# CH32V407WEU-R0.net
KiCad netlist of a schematic drawn in Altium Designer
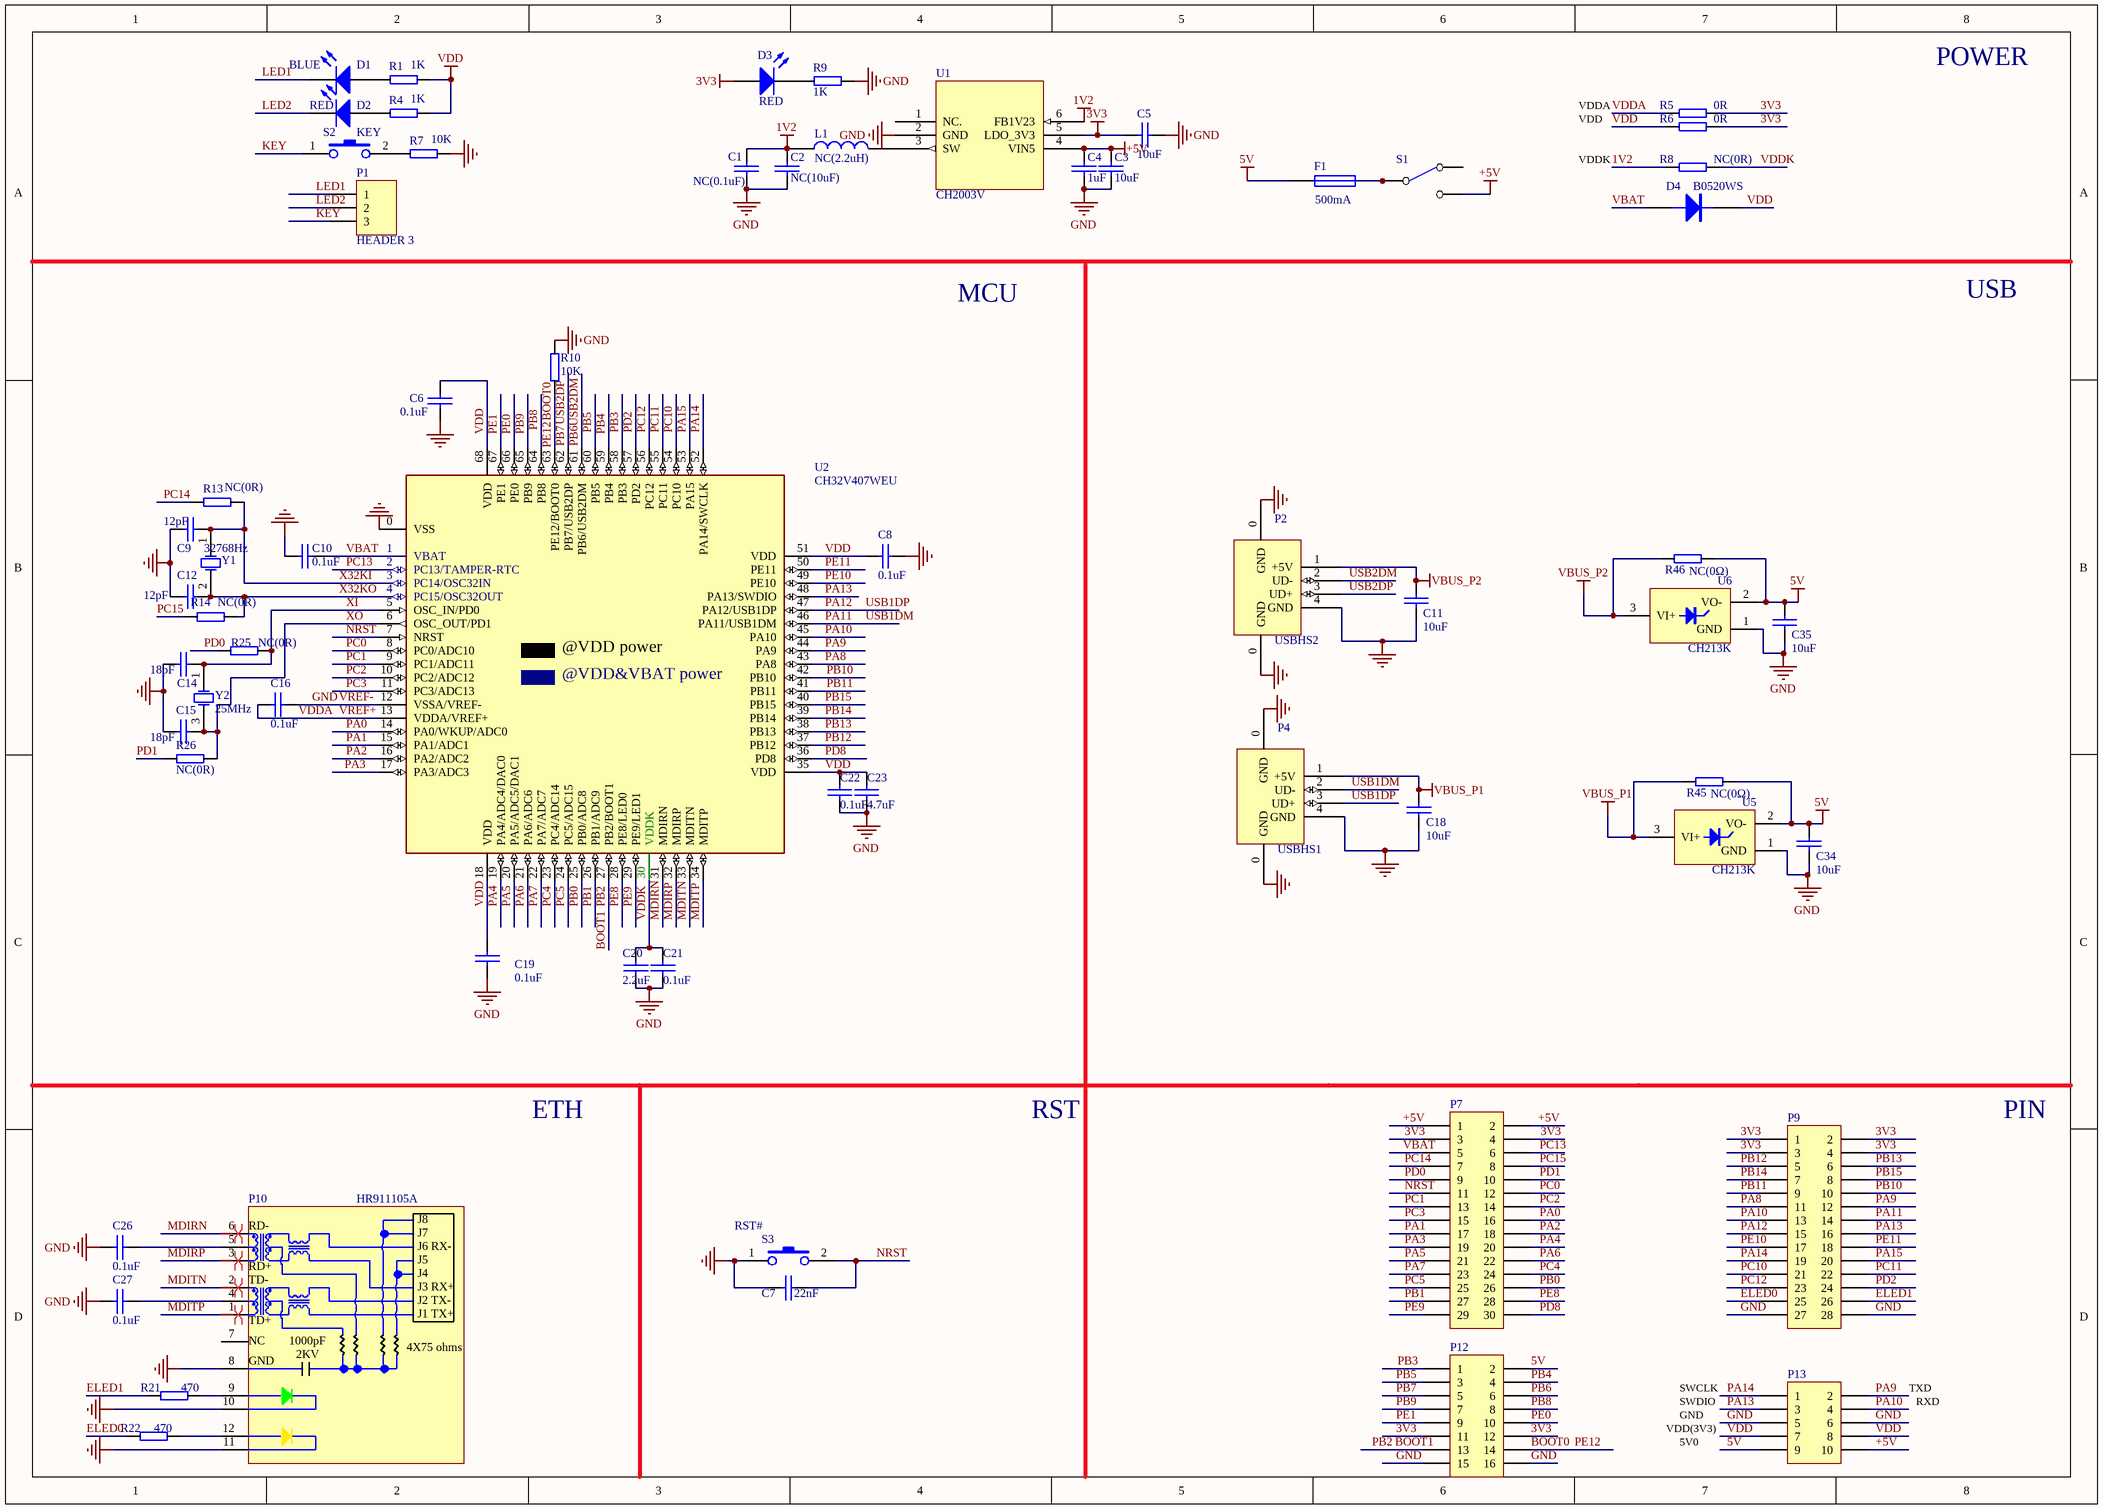
[diagram p0: CH32V407WEU-R0.SchDoc]

(export (version "E")
  (design (tool "Eeschema 10.0.6"))
  (components
    (comp (ref "C1")
      (value "NC(0.1uF)")
      (footprint "0402_C")
      (description "Capacitor")
      (libsource (lib "") (part "CAP_2"))
    )
    (comp (ref "C2")
      (value "NC(10uF)")
      (footprint "0603_C")
      (description "Capacitor")
      (libsource (lib "") (part "CAP_1"))
    )
    (comp (ref "C3")
      (value "10uF")
      (footprint "0603_C")
      (description "Capacitor")
      (libsource (lib "") (part "CAP_1"))
    )
    (comp (ref "C4")
      (value "1uF")
      (footprint "0402_C")
      (description "Capacitor")
      (libsource (lib "") (part "CAP_2"))
    )
    (comp (ref "C5")
      (value "10uF")
      (footprint "0603_C")
      (description "Capacitor")
      (libsource (lib "") (part "CAP_1"))
    )
    (comp (ref "C6")
      (value "0.1uF")
      (footprint "0402_C")
      (description "Capacitor")
      (libsource (lib "") (part "CAP_1"))
    )
    (comp (ref "C7")
      (value "22nF")
      (footprint "0402_C")
      (description "Capacitor")
      (libsource (lib "*") (part "CAP"))
    )
    (comp (ref "C8")
      (value "0.1uF")
      (footprint "0402_C")
      (description "Capacitor")
      (libsource (lib "") (part "CAP_1"))
    )
    (comp (ref "C9")
      (value "12pF")
      (footprint "0402_C")
      (description "Capacitor")
      (libsource (lib "") (part "CAP_1"))
    )
    (comp (ref "C10")
      (value "0.1uF")
      (footprint "0402_C")
      (description "Capacitor")
      (libsource (lib "") (part "CAP_1"))
    )
    (comp (ref "C11")
      (value "10uF")
      (footprint "0603_C")
      (description "Capacitor")
      (libsource (lib "*") (part "CAP"))
    )
    (comp (ref "C12")
      (value "12pF")
      (footprint "0402_C")
      (description "Capacitor")
      (libsource (lib "") (part "CAP_1"))
    )
    (comp (ref "C14")
      (value "18pF")
      (footprint "0402_C")
      (description "Capacitor")
      (libsource (lib "") (part "CAP_1"))
    )
    (comp (ref "C15")
      (value "18pF")
      (footprint "0402_C")
      (description "Capacitor")
      (libsource (lib "") (part "CAP_1"))
    )
    (comp (ref "C16")
      (value "0.1uF")
      (footprint "0402_C")
      (description "Capacitor")
      (libsource (lib "") (part "CAP_1"))
    )
    (comp (ref "C18")
      (value "10uF")
      (footprint "0603_C")
      (description "Capacitor")
      (libsource (lib "*") (part "CAP"))
    )
    (comp (ref "C19")
      (value "0.1uF")
      (footprint "0402_C")
      (description "Capacitor")
      (libsource (lib "") (part "CAP_1"))
    )
    (comp (ref "C20")
      (value "2.2uF")
      (footprint "0402_C")
      (description "Capacitor")
      (libsource (lib "") (part "CAP_1"))
    )
    (comp (ref "C21")
      (value "0.1uF")
      (footprint "0402_C")
      (description "Capacitor")
      (libsource (lib "") (part "CAP_1"))
    )
    (comp (ref "C22")
      (value "0.1uF")
      (footprint "0402_C")
      (description "Capacitor")
      (libsource (lib "") (part "CAP_1"))
    )
    (comp (ref "C23")
      (value "4.7uF")
      (footprint "0402_C")
      (description "Capacitor")
      (libsource (lib "") (part "CAP_1"))
    )
    (comp (ref "C26")
      (value "0.1uF")
      (footprint "0402_C")
      (description "Capacitor")
      (libsource (lib "wch_sch_others") (part "CAP"))
    )
    (comp (ref "C27")
      (value "0.1uF")
      (footprint "0402_C")
      (description "Capacitor")
      (libsource (lib "wch_sch_others") (part "CAP"))
    )
    (comp (ref "C34")
      (value "10uF")
      (footprint "0603_C")
      (description "Capacitor")
      (libsource (lib "*") (part "CAP"))
    )
    (comp (ref "C35")
      (value "10uF")
      (footprint "0603_C")
      (description "Capacitor")
      (libsource (lib "*") (part "CAP"))
    )
    (comp (ref "D1")
      (value "BLUE")
      (footprint "0603+")
      (description "Typical INFRARED GaAs LED")
      (fields (field (name "PUBLISHER") "Altium Limited"))
      (libsource (lib "*") (part "LED0"))
    )
    (comp (ref "D2")
      (value "RED")
      (footprint "0603+")
      (description "Typical INFRARED GaAs LED")
      (fields (field (name "PUBLISHER") "Altium Limited"))
      (libsource (lib "*") (part "LED0"))
    )
    (comp (ref "D3")
      (value "RED")
      (footprint "0603+")
      (description "Typical INFRARED GaAs LED")
      (fields (field (name "PUBLISHER") "Altium Limited"))
      (libsource (lib "*") (part "LED0"))
    )
    (comp (ref "D4")
      (value "B0520WS")
      (footprint "SOD-323")
      (description "Diode")
      (libsource (lib "*") (part "DIODE"))
    )
    (comp (ref "F1")
      (value "500mA")
      (footprint "0603")
      (description "Fuse")
      (libsource (lib "wch_sch_others") (part "FUSE1"))
    )
    (comp (ref "L1") (value "NC(2.2uH)") (footprint "CD32") (libsource (lib "*") (part "INDUCTOR")))
    (comp (ref "P1")
      (value "HEADER 3")
      (footprint "SIP3-2.54MM")
      (description "Header, 3-Pin")
      (libsource (lib "wch_sch_others") (part "HEADER 3"))
    )
    (comp (ref "P2")
      (value "USBHS2")
      (footprint "USBAF")
      (description "USB Port")
      (libsource (lib "*") (part "USB"))
    )
    (comp (ref "P4")
      (value "USBHS1")
      (footprint "USBAF")
      (description "USB Port")
      (libsource (lib "*") (part "USB"))
    )
    (comp (ref "P7")
      (value "HEADER 15x2")
      (footprint "MYPCB:IDC30-2.54MM")
      (description "Header, 15-Pin, Dual row")
      (libsource (lib "wch_sch_others") (part "HEADER 15x2"))
    )
    (comp (ref "P9")
      (value "HEADER 14x2")
      (footprint "MYPCB:IDC28-2.54MM")
      (description "Header, 14-Pin, Dual row")
      (libsource (lib "wch_sch_others") (part "HEADER 14x2"))
    )
    (comp (ref "P10") (value "HR911105A") (footprint "HR911105A") (libsource (lib "*") (part "HR911105A")))
    (comp (ref "P12")
      (value "Ppin")
      (footprint "IDC16-2.54mm")
      (description "Header, 8-Pin, Dual row, Right Angle")
      (fields (field (name "PUBLISHER") "Altium Limited"))
      (libsource (lib "Miscellaneous Connectors") (part "Header 8X2H"))
    )
    (comp (ref "P13")
      (value "LINK")
      (footprint "IDC10-2.54mm")
      (description "Header, 5-Pin, Dual row, Right Angle")
      (fields (field (name "PUBLISHER") "Altium Limited"))
      (libsource (lib "Miscellaneous Connectors") (part "Header 5X2H"))
    )
    (comp (ref "R1") (value "1K") (footprint "0402") (libsource (lib "wch_sch_others") (part "RES")))
    (comp (ref "R4") (value "1K") (footprint "0402") (libsource (lib "wch_sch_others") (part "RES")))
    (comp (ref "R5") (value "0R") (footprint "0402") (libsource (lib "*") (part "R")))
    (comp (ref "R6") (value "0R") (footprint "0402") (libsource (lib "*") (part "R")))
    (comp (ref "R7") (value "10K") (footprint "0402") (libsource (lib "wch_sch_others") (part "RES")))
    (comp (ref "R8") (value "NC(0R)") (footprint "0402") (libsource (lib "*") (part "R")))
    (comp (ref "R9") (value "1K") (footprint "0402") (libsource (lib "wch_sch_others") (part "RES")))
    (comp (ref "R10") (value "10K") (footprint "0402") (libsource (lib "wch_sch_others") (part "RES")))
    (comp (ref "R13") (value "NC(0R)") (footprint "0402") (libsource (lib "wch_sch_others") (part "RES")))
    (comp (ref "R14") (value "NC(0R)") (footprint "0402") (libsource (lib "wch_sch_others") (part "RES")))
    (comp (ref "R21") (value "470") (footprint "0402") (libsource (lib "wch_sch_others") (part "RES")))
    (comp (ref "R22") (value "470") (footprint "0402") (libsource (lib "wch_sch_others") (part "RES")))
    (comp (ref "R25") (value "NC(0R)") (footprint "0402") (libsource (lib "wch_sch_others") (part "RES")))
    (comp (ref "R26") (value "NC(0R)") (footprint "0402") (libsource (lib "wch_sch_others") (part "RES")))
    (comp (ref "R45") (value "NC(0Ω)") (footprint "0402") (libsource (lib "wch_sch_others") (part "RES")))
    (comp (ref "R46") (value "NC(0Ω)") (footprint "0402") (libsource (lib "wch_sch_others") (part "RES")))
    (comp (ref "S1") (value "SW SPDT") (footprint "SW1") (libsource (lib "*") (part "SW SPDT")))
    (comp (ref "S2")
      (value "KEY")
      (footprint "SMD_6.1x3.65x2.5mm-KEY")
      (libsource (lib "wch_sch_others") (part "KEY1"))
    )
    (comp (ref "S3")
      (value "RST#")
      (footprint "SMD_6.1x3.65x2.5mm-KEY")
      (libsource (lib "wch_sch_others") (part "KEY1"))
    )
    (comp (ref "U1")
      (value "CH2003V")
      (footprint "SOT-23-6")
      (description "Step-Down DC-DC Converter, 5V input, 1.23V * 800mA output, with LDO 3.3V * 200mA")
      (libsource (lib "CHXXX") (part "CH2003V"))
    )
    (comp (ref "U2")
      (value "CH32V407WEU")
      (footprint "QFN68_8X8")
      (description "RISC-V FPU HD-MCU, 175MHz, USB_480M, 100M Ethernet & Phy, CAN, ADC, DAC")
      (libsource (lib "CHXXX") (part "CH32V407WEU"))
    )
    (comp (ref "U5")
      (value "CH213K")
      (footprint "SOT-23-3")
      (description "Ideal Diode 5V*1A")
      (libsource (lib "*") (part "CH213K"))
    )
    (comp (ref "U6")
      (value "CH213K")
      (footprint "SOT-23-3")
      (description "Ideal Diode 5V*1A")
      (libsource (lib "*") (part "CH213K"))
    )
    (comp (ref "Y1")
      (value "32768Hz")
      (footprint "FC-135")
      (description "Crystal Oscillator")
      (fields (field (name "PUBLISHER") "Altium Limited"))
      (libsource (lib "") (part "XTAL_1"))
    )
    (comp (ref "Y2")
      (value "25MHz")
      (footprint "XT3225")
      (description "Crystal Oscillator")
      (fields (field (name "PUBLISHER") "Altium Limited"))
      (libsource (lib "*") (part "XTAL"))
    )
  )
  (nets
    (net (code "1") (name "+5V") (class "Default")
      (node (ref "C3") (pin "2") (pinfunction "2_2") (pintype "passive"))
      (node (ref "C4") (pin "2") (pinfunction "2_2") (pintype "passive"))
      (node (ref "P13") (pin "10") (pinfunction "10_10") (pintype "passive"))
      (node (ref "P7") (pin "1") (pinfunction "1_1") (pintype "passive"))
      (node (ref "P7") (pin "2") (pinfunction "2_2") (pintype "passive"))
      (node (ref "S1") (pin "2") (pinfunction "NC_2") (pintype "passive"))
      (node (ref "U1") (pin "4") (pinfunction "VIN5_4") (pintype "power_in"))
    )
    (net (code "3") (name "/BOOT0") (class "Default")
      (node (ref "P12") (pin "14") (pinfunction "14_14") (pintype "passive"))
      (node (ref "R10") (pin "2") (pintype "passive"))
      (node (ref "U2") (pin "63") (pinfunction "PE12/BOOT0_63") (pintype "bidirectional"))
    )
    (net (code "4") (name "/BOOT1") (class "Default")
      (node (ref "P12") (pin "13") (pinfunction "13_13") (pintype "passive"))
      (node (ref "U2") (pin "27") (pinfunction "PB2/BOOT1_27") (pintype "bidirectional"))
    )
    (net (code "5") (name "/ELED0") (class "Default")
      (node (ref "P9") (pin "25") (pinfunction "25_25") (pintype "passive"))
      (node (ref "R22") (pin "1") (pintype "passive"))
    )
    (net (code "6") (name "/ELED1") (class "Default")
      (node (ref "P9") (pin "26") (pinfunction "26_26") (pintype "passive"))
      (node (ref "R21") (pin "1") (pintype "passive"))
    )
    (net (code "7") (name "/KEY") (class "Default")
      (node (ref "P1") (pin "3") (pinfunction "3_3") (pintype "passive"))
      (node (ref "S2") (pin "1") (pinfunction "1_1") (pintype "passive"))
    )
    (net (code "8") (name "/LED1") (class "Default")
      (node (ref "D1") (pin "2") (pinfunction "K_2") (pintype "passive"))
      (node (ref "P1") (pin "1") (pinfunction "1_1") (pintype "passive"))
    )
    (net (code "9") (name "/LED2") (class "Default")
      (node (ref "D2") (pin "2") (pinfunction "K_2") (pintype "passive"))
      (node (ref "P1") (pin "2") (pinfunction "2_2") (pintype "passive"))
    )
    (net (code "10") (name "/MDIRN") (class "Default")
      (node (ref "P10") (pin "6") (pintype "passive"))
      (node (ref "U2") (pin "31") (pinfunction "MDIRN_31") (pintype "bidirectional"))
    )
    (net (code "11") (name "/MDIRP") (class "Default")
      (node (ref "P10") (pin "3") (pintype "passive"))
      (node (ref "U2") (pin "32") (pinfunction "MDIRP_32") (pintype "bidirectional"))
    )
    (net (code "12") (name "/MDITN") (class "Default")
      (node (ref "P10") (pin "2") (pintype "passive"))
      (node (ref "U2") (pin "33") (pinfunction "MDITN_33") (pintype "bidirectional"))
    )
    (net (code "13") (name "/MDITP") (class "Default")
      (node (ref "P10") (pin "1") (pintype "passive"))
      (node (ref "U2") (pin "34") (pinfunction "MDITP_34") (pintype "bidirectional"))
    )
    (net (code "14") (name "/NRST") (class "Default")
      (node (ref "C7") (pin "2") (pinfunction "2_2") (pintype "passive"))
      (node (ref "P7") (pin "11") (pinfunction "11_11") (pintype "passive"))
      (node (ref "S3") (pin "2") (pinfunction "2_2") (pintype "passive"))
      (node (ref "U2") (pin "7") (pinfunction "NRST_7") (pintype "input"))
    )
    (net (code "15") (name "/PA0") (class "Default")
      (node (ref "P7") (pin "16") (pinfunction "16_16") (pintype "passive"))
      (node (ref "U2") (pin "14") (pinfunction "PA0/WKUP/ADC0_14") (pintype "bidirectional"))
    )
    (net (code "16") (name "/PA1") (class "Default")
      (node (ref "P7") (pin "17") (pinfunction "17_17") (pintype "passive"))
      (node (ref "U2") (pin "15") (pinfunction "PA1/ADC1_15") (pintype "bidirectional"))
    )
    (net (code "17") (name "/PA2") (class "Default")
      (node (ref "P7") (pin "18") (pinfunction "18_18") (pintype "passive"))
      (node (ref "U2") (pin "16") (pinfunction "PA2/ADC2_16") (pintype "bidirectional"))
    )
    (net (code "18") (name "/PA3") (class "Default")
      (node (ref "P7") (pin "19") (pinfunction "19_19") (pintype "passive"))
      (node (ref "U2") (pin "17") (pinfunction "PA3/ADC3_17") (pintype "bidirectional"))
    )
    (net (code "19") (name "/PA4") (class "Default")
      (node (ref "P7") (pin "20") (pinfunction "20_20") (pintype "passive"))
      (node (ref "U2") (pin "19") (pinfunction "PA4/ADC4/DAC0_19") (pintype "bidirectional"))
    )
    (net (code "20") (name "/PA5") (class "Default")
      (node (ref "P7") (pin "21") (pinfunction "21_21") (pintype "passive"))
      (node (ref "U2") (pin "20") (pinfunction "PA5/ADC5/DAC1_20") (pintype "bidirectional"))
    )
    (net (code "21") (name "/PA6") (class "Default")
      (node (ref "P7") (pin "22") (pinfunction "22_22") (pintype "passive"))
      (node (ref "U2") (pin "21") (pinfunction "PA6/ADC6_21") (pintype "bidirectional"))
    )
    (net (code "22") (name "/PA7") (class "Default")
      (node (ref "P7") (pin "23") (pinfunction "23_23") (pintype "passive"))
      (node (ref "U2") (pin "22") (pinfunction "PA7/ADC7_22") (pintype "bidirectional"))
    )
    (net (code "23") (name "/PA8") (class "Default")
      (node (ref "P9") (pin "11") (pinfunction "11_11") (pintype "passive"))
      (node (ref "U2") (pin "43") (pinfunction "PA8_43") (pintype "bidirectional"))
    )
    (net (code "24") (name "/PA9") (class "Default")
      (node (ref "P13") (pin "2") (pinfunction "2_2") (pintype "passive"))
      (node (ref "P9") (pin "12") (pinfunction "12_12") (pintype "passive"))
      (node (ref "U2") (pin "44") (pinfunction "PA9_44") (pintype "bidirectional"))
    )
    (net (code "25") (name "/PA10") (class "Default")
      (node (ref "P13") (pin "4") (pinfunction "4_4") (pintype "passive"))
      (node (ref "P9") (pin "13") (pinfunction "13_13") (pintype "passive"))
      (node (ref "U2") (pin "45") (pinfunction "PA10_45") (pintype "bidirectional"))
    )
    (net (code "26") (name "/PA11") (class "Default")
      (node (ref "P4") (pin "2") (pinfunction "UD-_2") (pintype "bidirectional"))
      (node (ref "P9") (pin "14") (pinfunction "14_14") (pintype "passive"))
      (node (ref "U2") (pin "46") (pinfunction "PA11/USB1DM_46") (pintype "bidirectional"))
    )
    (net (code "27") (name "/PA12") (class "Default")
      (node (ref "P4") (pin "3") (pinfunction "UD+_3") (pintype "bidirectional"))
      (node (ref "P9") (pin "15") (pinfunction "15_15") (pintype "passive"))
      (node (ref "U2") (pin "47") (pinfunction "PA12/USB1DP_47") (pintype "bidirectional"))
    )
    (net (code "28") (name "/PA13") (class "Default")
      (node (ref "P13") (pin "3") (pinfunction "3_3") (pintype "passive"))
      (node (ref "P9") (pin "16") (pinfunction "16_16") (pintype "passive"))
      (node (ref "U2") (pin "48") (pinfunction "PA13/SWDIO_48") (pintype "bidirectional"))
    )
    (net (code "29") (name "/PA14") (class "Default")
      (node (ref "P13") (pin "1") (pinfunction "1_1") (pintype "passive"))
      (node (ref "P9") (pin "19") (pinfunction "19_19") (pintype "passive"))
      (node (ref "U2") (pin "52") (pinfunction "PA14/SWCLK_52") (pintype "bidirectional"))
    )
    (net (code "30") (name "/PA15") (class "Default")
      (node (ref "P9") (pin "20") (pinfunction "20_20") (pintype "passive"))
      (node (ref "U2") (pin "53") (pinfunction "PA15_53") (pintype "bidirectional"))
    )
    (net (code "31") (name "/PB0") (class "Default")
      (node (ref "P7") (pin "26") (pinfunction "26_26") (pintype "passive"))
      (node (ref "U2") (pin "25") (pinfunction "PB0/ADC8_25") (pintype "bidirectional"))
    )
    (net (code "32") (name "/PB1") (class "Default")
      (node (ref "P7") (pin "27") (pinfunction "27_27") (pintype "passive"))
      (node (ref "U2") (pin "26") (pinfunction "PB1/ADC9_26") (pintype "bidirectional"))
    )
    (net (code "33") (name "/PB3") (class "Default")
      (node (ref "P12") (pin "1") (pinfunction "1_1") (pintype "passive"))
      (node (ref "U2") (pin "58") (pinfunction "PB3_58") (pintype "bidirectional"))
    )
    (net (code "34") (name "/PB4") (class "Default")
      (node (ref "P12") (pin "4") (pinfunction "4_4") (pintype "passive"))
      (node (ref "U2") (pin "59") (pinfunction "PB4_59") (pintype "bidirectional"))
    )
    (net (code "35") (name "/PB5") (class "Default")
      (node (ref "P12") (pin "3") (pinfunction "3_3") (pintype "passive"))
      (node (ref "U2") (pin "60") (pinfunction "PB5_60") (pintype "bidirectional"))
    )
    (net (code "36") (name "/PB6") (class "Default")
      (node (ref "P12") (pin "6") (pinfunction "6_6") (pintype "passive"))
      (node (ref "P2") (pin "2") (pinfunction "UD-_2") (pintype "bidirectional"))
      (node (ref "U2") (pin "61") (pinfunction "PB6/USB2DM_61") (pintype "bidirectional"))
    )
    (net (code "37") (name "/PB7") (class "Default")
      (node (ref "P12") (pin "5") (pinfunction "5_5") (pintype "passive"))
      (node (ref "P2") (pin "3") (pinfunction "UD+_3") (pintype "bidirectional"))
      (node (ref "U2") (pin "62") (pinfunction "PB7/USB2DP_62") (pintype "bidirectional"))
    )
    (net (code "38") (name "/PB8") (class "Default")
      (node (ref "P12") (pin "8") (pinfunction "8_8") (pintype "passive"))
      (node (ref "U2") (pin "64") (pinfunction "PB8_64") (pintype "bidirectional"))
    )
    (net (code "39") (name "/PB9") (class "Default")
      (node (ref "P12") (pin "7") (pinfunction "7_7") (pintype "passive"))
      (node (ref "U2") (pin "65") (pinfunction "PB9_65") (pintype "bidirectional"))
    )
    (net (code "40") (name "/PB10") (class "Default")
      (node (ref "P9") (pin "10") (pinfunction "10_10") (pintype "passive"))
      (node (ref "U2") (pin "42") (pinfunction "PB10_42") (pintype "bidirectional"))
    )
    (net (code "41") (name "/PB11") (class "Default")
      (node (ref "P9") (pin "9") (pinfunction "9_9") (pintype "passive"))
      (node (ref "U2") (pin "41") (pinfunction "PB11_41") (pintype "bidirectional"))
    )
    (net (code "42") (name "/PB12") (class "Default")
      (node (ref "P9") (pin "5") (pinfunction "5_5") (pintype "passive"))
      (node (ref "U2") (pin "37") (pinfunction "PB12_37") (pintype "bidirectional"))
    )
    (net (code "43") (name "/PB13") (class "Default")
      (node (ref "P9") (pin "6") (pinfunction "6_6") (pintype "passive"))
      (node (ref "U2") (pin "38") (pinfunction "PB13_38") (pintype "bidirectional"))
    )
    (net (code "44") (name "/PB14") (class "Default")
      (node (ref "P9") (pin "7") (pinfunction "7_7") (pintype "passive"))
      (node (ref "U2") (pin "39") (pinfunction "PB14_39") (pintype "bidirectional"))
    )
    (net (code "45") (name "/PB15") (class "Default")
      (node (ref "P9") (pin "8") (pinfunction "8_8") (pintype "passive"))
      (node (ref "U2") (pin "40") (pinfunction "PB15_40") (pintype "bidirectional"))
    )
    (net (code "46") (name "/PC0") (class "Default")
      (node (ref "P7") (pin "12") (pinfunction "12_12") (pintype "passive"))
      (node (ref "U2") (pin "8") (pinfunction "PC0/ADC10_8") (pintype "bidirectional"))
    )
    (net (code "47") (name "/PC1") (class "Default")
      (node (ref "P7") (pin "13") (pinfunction "13_13") (pintype "passive"))
      (node (ref "U2") (pin "9") (pinfunction "PC1/ADC11_9") (pintype "bidirectional"))
    )
    (net (code "48") (name "/PC2") (class "Default")
      (node (ref "P7") (pin "14") (pinfunction "14_14") (pintype "passive"))
      (node (ref "U2") (pin "10") (pinfunction "PC2/ADC12_10") (pintype "bidirectional"))
    )
    (net (code "49") (name "/PC3") (class "Default")
      (node (ref "P7") (pin "15") (pinfunction "15_15") (pintype "passive"))
      (node (ref "U2") (pin "11") (pinfunction "PC3/ADC13_11") (pintype "bidirectional"))
    )
    (net (code "50") (name "/PC4") (class "Default")
      (node (ref "P7") (pin "24") (pinfunction "24_24") (pintype "passive"))
      (node (ref "U2") (pin "23") (pinfunction "PC4/ADC14_23") (pintype "bidirectional"))
    )
    (net (code "51") (name "/PC5") (class "Default")
      (node (ref "P7") (pin "25") (pinfunction "25_25") (pintype "passive"))
      (node (ref "U2") (pin "24") (pinfunction "PC5/ADC15_24") (pintype "bidirectional"))
    )
    (net (code "52") (name "/PC10") (class "Default")
      (node (ref "P9") (pin "21") (pinfunction "21_21") (pintype "passive"))
      (node (ref "U2") (pin "54") (pinfunction "PC10_54") (pintype "bidirectional"))
    )
    (net (code "53") (name "/PC11") (class "Default")
      (node (ref "P9") (pin "22") (pinfunction "22_22") (pintype "passive"))
      (node (ref "U2") (pin "55") (pinfunction "PC11_55") (pintype "bidirectional"))
    )
    (net (code "54") (name "/PC12") (class "Default")
      (node (ref "P9") (pin "23") (pinfunction "23_23") (pintype "passive"))
      (node (ref "U2") (pin "56") (pinfunction "PC12_56") (pintype "bidirectional"))
    )
    (net (code "55") (name "/PC13") (class "Default")
      (node (ref "P7") (pin "6") (pinfunction "6_6") (pintype "passive"))
      (node (ref "U2") (pin "2") (pinfunction "PC13/TAMPER-RTC_2") (pintype "bidirectional"))
    )
    (net (code "56") (name "/PC14") (class "Default")
      (node (ref "P7") (pin "7") (pinfunction "7_7") (pintype "passive"))
      (node (ref "R13") (pin "1") (pintype "passive"))
    )
    (net (code "57") (name "/PC15") (class "Default")
      (node (ref "P7") (pin "8") (pinfunction "8_8") (pintype "passive"))
      (node (ref "R14") (pin "1") (pintype "passive"))
    )
    (net (code "58") (name "/PD0") (class "Default")
      (node (ref "P7") (pin "9") (pinfunction "9_9") (pintype "passive"))
      (node (ref "R25") (pin "1") (pintype "passive"))
    )
    (net (code "59") (name "/PD1") (class "Default")
      (node (ref "P7") (pin "10") (pinfunction "10_10") (pintype "passive"))
      (node (ref "R26") (pin "2") (pintype "passive"))
    )
    (net (code "60") (name "/PD2") (class "Default")
      (node (ref "P9") (pin "24") (pinfunction "24_24") (pintype "passive"))
      (node (ref "U2") (pin "57") (pinfunction "PD2_57") (pintype "bidirectional"))
    )
    (net (code "61") (name "/PD8") (class "Default")
      (node (ref "P7") (pin "30") (pinfunction "30_30") (pintype "passive"))
      (node (ref "U2") (pin "36") (pinfunction "PD8_36") (pintype "bidirectional"))
    )
    (net (code "62") (name "/PE0") (class "Default")
      (node (ref "P12") (pin "10") (pinfunction "10_10") (pintype "passive"))
      (node (ref "U2") (pin "66") (pinfunction "PE0_66") (pintype "bidirectional"))
    )
    (net (code "63") (name "/PE1") (class "Default")
      (node (ref "P12") (pin "9") (pinfunction "9_9") (pintype "passive"))
      (node (ref "U2") (pin "67") (pinfunction "PE1_67") (pintype "bidirectional"))
    )
    (net (code "64") (name "/PE8") (class "Default")
      (node (ref "P7") (pin "28") (pinfunction "28_28") (pintype "passive"))
      (node (ref "U2") (pin "28") (pinfunction "PE8/LED0_28") (pintype "bidirectional"))
    )
    (net (code "65") (name "/PE9") (class "Default")
      (node (ref "P7") (pin "29") (pinfunction "29_29") (pintype "passive"))
      (node (ref "U2") (pin "29") (pinfunction "PE9/LED1_29") (pintype "bidirectional"))
    )
    (net (code "66") (name "/PE10") (class "Default")
      (node (ref "P9") (pin "17") (pinfunction "17_17") (pintype "passive"))
      (node (ref "U2") (pin "49") (pinfunction "PE10_49") (pintype "bidirectional"))
    )
    (net (code "67") (name "/PE11") (class "Default")
      (node (ref "P9") (pin "18") (pinfunction "18_18") (pintype "passive"))
      (node (ref "U2") (pin "50") (pinfunction "PE11_50") (pintype "bidirectional"))
    )
    (net (code "68") (name "/VBAT") (class "Default")
      (node (ref "C10") (pin "2") (pinfunction "2_2") (pintype "passive"))
      (node (ref "D4") (pin "1") (pinfunction "A_1") (pintype "passive"))
      (node (ref "P7") (pin "5") (pinfunction "5_5") (pintype "passive"))
      (node (ref "U2") (pin "1") (pinfunction "VBAT_1") (pintype "power_in"))
    )
    (net (code "69") (name "/VDDA") (class "Default")
      (node (ref "C16") (pin "1") (pinfunction "1_1") (pintype "passive"))
      (node (ref "R5") (pin "2") (pinfunction "2_2") (pintype "passive"))
      (node (ref "U2") (pin "13") (pinfunction "VDDA/VREF+_13") (pintype "power_in"))
    )
    (net (code "70") (name "/VDDK") (class "Default")
      (node (ref "C20") (pin "2") (pinfunction "2_2") (pintype "passive"))
      (node (ref "C21") (pin "2") (pinfunction "2_2") (pintype "passive"))
      (node (ref "R8") (pin "1") (pinfunction "1_1") (pintype "passive"))
      (node (ref "U2") (pin "30") (pinfunction "VDDK_30") (pintype "power_in"))
    )
    (net (code "71") (name "/X32KI") (class "Default")
      (node (ref "C9") (pin "2") (pinfunction "2_2") (pintype "passive"))
      (node (ref "R13") (pin "2") (pintype "passive"))
      (node (ref "U2") (pin "3") (pinfunction "PC14/OSC32IN_3") (pintype "bidirectional"))
      (node (ref "Y1") (pin "1") (pinfunction "OSC1_1") (pintype "passive"))
    )
    (net (code "72") (name "/X32KO") (class "Default")
      (node (ref "C12") (pin "2") (pinfunction "2_2") (pintype "passive"))
      (node (ref "R14") (pin "2") (pintype "passive"))
      (node (ref "U2") (pin "4") (pinfunction "PC15/OSC32OUT_4") (pintype "bidirectional"))
      (node (ref "Y1") (pin "2") (pinfunction "OSC2_2") (pintype "passive"))
    )
    (net (code "73") (name "/XI") (class "Default")
      (node (ref "C14") (pin "2") (pinfunction "2_2") (pintype "passive"))
      (node (ref "R25") (pin "2") (pintype "passive"))
      (node (ref "U2") (pin "5") (pinfunction "OSC_IN/PD0_5") (pintype "input"))
      (node (ref "Y2") (pin "1") (pinfunction "OSC1_1") (pintype "passive"))
    )
    (net (code "74") (name "/XO") (class "Default")
      (node (ref "C15") (pin "2") (pinfunction "2_2") (pintype "passive"))
      (node (ref "R26") (pin "1") (pintype "passive"))
      (node (ref "U2") (pin "6") (pinfunction "OSC_OUT/PD1_6") (pintype "output"))
      (node (ref "Y2") (pin "3") (pinfunction "OSC2_3") (pintype "passive"))
    )
    (net (code "75") (name "1V2") (class "Default")
      (node (ref "C1") (pin "2") (pinfunction "2_2") (pintype "passive"))
      (node (ref "C2") (pin "2") (pinfunction "2_2") (pintype "passive"))
      (node (ref "L1") (pin "2") (pinfunction "2_2") (pintype "passive"))
      (node (ref "R8") (pin "2") (pinfunction "2_2") (pintype "passive"))
      (node (ref "U1") (pin "6") (pinfunction "FB1V23_6") (pintype "input"))
    )
    (net (code "76") (name "3V3") (class "Default")
      (node (ref "C5") (pin "2") (pinfunction "2_2") (pintype "passive"))
      (node (ref "D3") (pin "1") (pinfunction "A_1") (pintype "passive"))
      (node (ref "P12") (pin "11") (pinfunction "11_11") (pintype "passive"))
      (node (ref "P12") (pin "12") (pinfunction "12_12") (pintype "passive"))
      (node (ref "P7") (pin "3") (pinfunction "3_3") (pintype "passive"))
      (node (ref "P7") (pin "4") (pinfunction "4_4") (pintype "passive"))
      (node (ref "P9") (pin "1") (pinfunction "1_1") (pintype "passive"))
      (node (ref "P9") (pin "2") (pinfunction "2_2") (pintype "passive"))
      (node (ref "P9") (pin "3") (pinfunction "3_3") (pintype "passive"))
      (node (ref "P9") (pin "4") (pinfunction "4_4") (pintype "passive"))
      (node (ref "R5") (pin "1") (pinfunction "1_1") (pintype "passive"))
      (node (ref "R6") (pin "1") (pinfunction "1_1") (pintype "passive"))
      (node (ref "U1") (pin "5") (pinfunction "LDO_3V3_5") (pintype "power_in"))
    )
    (net (code "77") (name "5V") (class "Default")
      (node (ref "C34") (pin "1") (pinfunction "1_1") (pintype "passive"))
      (node (ref "C35") (pin "1") (pinfunction "1_1") (pintype "passive"))
      (node (ref "F1") (pin "1") (pinfunction "1_1") (pintype "passive"))
      (node (ref "P12") (pin "2") (pinfunction "2_2") (pintype "passive"))
      (node (ref "P13") (pin "9") (pinfunction "9_9") (pintype "passive"))
      (node (ref "R45") (pin "1") (pintype "passive"))
      (node (ref "R46") (pin "1") (pintype "passive"))
      (node (ref "U5") (pin "2") (pinfunction "VO-_2") (pintype "power_in"))
      (node (ref "U6") (pin "2") (pinfunction "VO-_2") (pintype "power_in"))
    )
    (net (code "78") (name "GND") (class "Default")
      (node (ref "C1") (pin "1") (pinfunction "1_1") (pintype "passive"))
      (node (ref "C10") (pin "1") (pinfunction "1_1") (pintype "passive"))
      (node (ref "C11") (pin "2") (pinfunction "2_2") (pintype "passive"))
      (node (ref "C12") (pin "1") (pinfunction "1_1") (pintype "passive"))
      (node (ref "C14") (pin "1") (pinfunction "1_1") (pintype "passive"))
      (node (ref "C15") (pin "1") (pinfunction "1_1") (pintype "passive"))
      (node (ref "C16") (pin "2") (pinfunction "2_2") (pintype "passive"))
      (node (ref "C18") (pin "2") (pinfunction "2_2") (pintype "passive"))
      (node (ref "C19") (pin "1") (pinfunction "1_1") (pintype "passive"))
      (node (ref "C2") (pin "1") (pinfunction "1_1") (pintype "passive"))
      (node (ref "C20") (pin "1") (pinfunction "1_1") (pintype "passive"))
      (node (ref "C21") (pin "1") (pinfunction "1_1") (pintype "passive"))
      (node (ref "C22") (pin "1") (pinfunction "1_1") (pintype "passive"))
      (node (ref "C23") (pin "1") (pinfunction "1_1") (pintype "passive"))
      (node (ref "C26") (pin "1") (pinfunction "1_1") (pintype "passive"))
      (node (ref "C27") (pin "1") (pinfunction "1_1") (pintype "passive"))
      (node (ref "C3") (pin "1") (pinfunction "1_1") (pintype "passive"))
      (node (ref "C34") (pin "2") (pinfunction "2_2") (pintype "passive"))
      (node (ref "C35") (pin "2") (pinfunction "2_2") (pintype "passive"))
      (node (ref "C4") (pin "1") (pinfunction "1_1") (pintype "passive"))
      (node (ref "C5") (pin "1") (pinfunction "1_1") (pintype "passive"))
      (node (ref "C6") (pin "1") (pinfunction "1_1") (pintype "passive"))
      (node (ref "C7") (pin "1") (pinfunction "1_1") (pintype "passive"))
      (node (ref "C8") (pin "2") (pinfunction "2_2") (pintype "passive"))
      (node (ref "C9") (pin "1") (pinfunction "1_1") (pintype "passive"))
      (node (ref "P10") (pin "10") (pintype "passive"))
      (node (ref "P10") (pin "11") (pintype "passive"))
      (node (ref "P10") (pin "8") (pintype "passive"))
      (node (ref "P12") (pin "15") (pinfunction "15_15") (pintype "passive"))
      (node (ref "P12") (pin "16") (pinfunction "16_16") (pintype "passive"))
      (node (ref "P13") (pin "5") (pinfunction "5_5") (pintype "passive"))
      (node (ref "P13") (pin "6") (pinfunction "6_6") (pintype "passive"))
      (node (ref "P2") (pin "0") (pinfunction "GND_0") (pintype "power_in"))
      (node (ref "P2") (pin "4") (pinfunction "GND_4") (pintype "power_in"))
      (node (ref "P4") (pin "0") (pinfunction "GND_0") (pintype "power_in"))
      (node (ref "P4") (pin "4") (pinfunction "GND_4") (pintype "power_in"))
      (node (ref "P9") (pin "27") (pinfunction "27_27") (pintype "passive"))
      (node (ref "P9") (pin "28") (pinfunction "28_28") (pintype "passive"))
      (node (ref "R10") (pin "1") (pintype "passive"))
      (node (ref "R7") (pin "1") (pintype "passive"))
      (node (ref "R9") (pin "2") (pintype "passive"))
      (node (ref "S3") (pin "1") (pinfunction "1_1") (pintype "passive"))
      (node (ref "U1") (pin "2") (pinfunction "GND_2") (pintype "power_in"))
      (node (ref "U2") (pin "0") (pinfunction "VSS_0") (pintype "power_in"))
      (node (ref "U2") (pin "12") (pinfunction "VSSA/VREF-_12") (pintype "power_in"))
      (node (ref "U5") (pin "1") (pinfunction "GND_1") (pintype "power_in"))
      (node (ref "U6") (pin "1") (pinfunction "GND_1") (pintype "power_in"))
    )
    (net (code "79") (name "Net-(C26-Pad2)") (class "Default")
      (node (ref "C26") (pin "2") (pinfunction "2_2") (pintype "passive"))
      (node (ref "P10") (pin "5") (pintype "passive"))
    )
    (net (code "80") (name "Net-(C27-Pad2)") (class "Default")
      (node (ref "C27") (pin "2") (pinfunction "2_2") (pintype "passive"))
      (node (ref "P10") (pin "4") (pintype "passive"))
    )
    (net (code "81") (name "Net-(D1-A)") (class "Default")
      (node (ref "D1") (pin "1") (pinfunction "A_1") (pintype "passive"))
      (node (ref "R1") (pin "2") (pintype "passive"))
    )
    (net (code "82") (name "Net-(D2-A)") (class "Default")
      (node (ref "D2") (pin "1") (pinfunction "A_1") (pintype "passive"))
      (node (ref "R4") (pin "2") (pintype "passive"))
    )
    (net (code "83") (name "Net-(D3-K)") (class "Default")
      (node (ref "D3") (pin "2") (pinfunction "K_2") (pintype "passive"))
      (node (ref "R9") (pin "1") (pintype "passive"))
    )
    (net (code "84") (name "Net-(P10-Pad9)") (class "Default")
      (node (ref "P10") (pin "9") (pintype "passive"))
      (node (ref "R21") (pin "2") (pintype "passive"))
    )
    (net (code "85") (name "Net-(P10-Pad12)") (class "Default")
      (node (ref "P10") (pin "12") (pintype "passive"))
      (node (ref "R22") (pin "2") (pintype "passive"))
    )
    (net (code "86") (name "Net-(R7-Pad2)") (class "Default")
      (node (ref "R7") (pin "2") (pintype "passive"))
      (node (ref "S2") (pin "2") (pinfunction "2_2") (pintype "passive"))
    )
    (net (code "87") (name "Net-(S1-COMMON)") (class "Default")
      (node (ref "F1") (pin "2") (pinfunction "2_2") (pintype "passive"))
      (node (ref "S1") (pin "1") (pinfunction "COMMON_1") (pintype "passive"))
    )
    (net (code "88") (name "Net-(U1-SW)") (class "Default")
      (node (ref "L1") (pin "1") (pinfunction "1_1") (pintype "passive"))
      (node (ref "U1") (pin "3") (pinfunction "SW_3") (pintype "output"))
    )
    (net (code "89") (name "VBUS_P1") (class "Default")
      (node (ref "C18") (pin "1") (pinfunction "1_1") (pintype "passive"))
      (node (ref "P4") (pin "1") (pinfunction "+5V_1") (pintype "power_in"))
      (node (ref "R45") (pin "2") (pintype "passive"))
      (node (ref "U5") (pin "3") (pinfunction "VI+_3") (pintype "power_in"))
    )
    (net (code "90") (name "VBUS_P2") (class "Default")
      (node (ref "C11") (pin "1") (pinfunction "1_1") (pintype "passive"))
      (node (ref "P2") (pin "1") (pinfunction "+5V_1") (pintype "power_in"))
      (node (ref "R46") (pin "2") (pintype "passive"))
      (node (ref "U6") (pin "3") (pinfunction "VI+_3") (pintype "power_in"))
    )
    (net (code "91") (name "VDD") (class "Default")
      (node (ref "C19") (pin "2") (pinfunction "2_2") (pintype "passive"))
      (node (ref "C22") (pin "2") (pinfunction "2_2") (pintype "passive"))
      (node (ref "C23") (pin "2") (pinfunction "2_2") (pintype "passive"))
      (node (ref "C6") (pin "2") (pinfunction "2_2") (pintype "passive"))
      (node (ref "C8") (pin "1") (pinfunction "1_1") (pintype "passive"))
      (node (ref "D4") (pin "2") (pinfunction "K_2") (pintype "passive"))
      (node (ref "P13") (pin "7") (pinfunction "7_7") (pintype "passive"))
      (node (ref "P13") (pin "8") (pinfunction "8_8") (pintype "passive"))
      (node (ref "R1") (pin "1") (pintype "passive"))
      (node (ref "R4") (pin "1") (pintype "passive"))
      (node (ref "R6") (pin "2") (pinfunction "2_2") (pintype "passive"))
      (node (ref "U2") (pin "18") (pinfunction "VDD_18") (pintype "power_in"))
      (node (ref "U2") (pin "35") (pinfunction "VDD_35") (pintype "power_in"))
      (node (ref "U2") (pin "51") (pinfunction "VDD_51") (pintype "power_in"))
      (node (ref "U2") (pin "68") (pinfunction "VDD_68") (pintype "power_in"))
    )
    (net (code "92") (name "unconnected-(P10-Pad7)") (class "Default")
      (node (ref "P10") (pin "7") (pintype "passive"))
    )
    (net (code "93") (name "unconnected-(S1-NO-Pad3)") (class "Default")
      (node (ref "S1") (pin "3") (pinfunction "NO_3") (pintype "passive"))
    )
    (net (code "94") (name "unconnected-(U1-NC.-Pad1)") (class "Default")
      (node (ref "U1") (pin "1") (pinfunction "NC._1") (pintype "passive"))
    )
  )
)
